# memory.net
KiCad netlist of a schematic drawn in Altium Designer
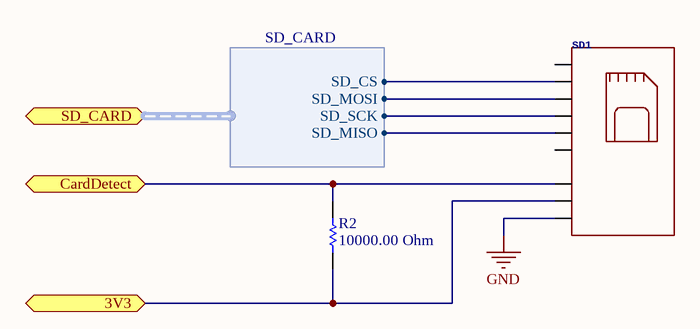
[diagram p0: memory.SchDoc]

(export (version "E")
  (design (tool "Eeschema 10.0.6"))
  (components
    (comp (ref "R2")
      (value "10000.00 Ohm")
      (footprint "RESC0402(1005)_N")
      (description "10K 0.063W 5% 0402 (1005 Metric)  SMD")
      (fields (field (name "POWER") "0.063 W") (field (name "TOLERANCE") "5 %"))
      (libsource (lib "Altium Content Vault") (part "CMP-1011-00081-1"))
    )
    (comp (ref "SD1")
      (value "Library:  MF_Connectors Description: SD Card Connector")
      (footprint "MF-MICROSD")
      (fields (field (name "HOUSEPART") "YES") (field (name "MPN") "MF-MICROSD"))
      (libsource (lib "MF_Connectors") (part "SD_CARD_SLOT_MICRO_RIGHT"))
    )
  )
  (nets
    (net (code "2") (name "/3V3") (class "Default")
      (node (ref "R2") (pin "1") (pinfunction "1_1") (pintype "passive"))
      (node (ref "SD1") (pin "PIN4") (pinfunction "3.3V_PIN4") (pintype "power_in"))
    )
    (net (code "3") (name "/CardDetect") (class "Default")
      (node (ref "R2") (pin "2") (pinfunction "2_2") (pintype "passive"))
      (node (ref "SD1") (pin "PIN9_PIN10") (pinfunction "CRD_DTCT_PIN9_PIN10") (pintype "passive"))
    )
    (net (code "4") (name "/SD_CS") (class "Default")
      (node (ref "SD1") (pin "PIN2") (pinfunction "CS_PIN2") (pintype "passive"))
    )
    (net (code "5") (name "/SD_MISO") (class "Default")
      (node (ref "SD1") (pin "PIN7") (pinfunction "D0_PIN7") (pintype "passive"))
    )
    (net (code "6") (name "/SD_MOSI") (class "Default")
      (node (ref "SD1") (pin "PIN3") (pinfunction "DI_PIN3") (pintype "passive"))
    )
    (net (code "7") (name "/SD_SCK") (class "Default")
      (node (ref "SD1") (pin "PIN5") (pinfunction "SCLK_PIN5") (pintype "passive"))
    )
    (net (code "9") (name "GND") (class "Default")
      (node (ref "SD1") (pin "G0_G1_PIN6") (pinfunction "GND_G0_G1_PIN6") (pintype "power_in"))
    )
    (net (code "10") (name "unconnected-(SD1-IRQ-PadPIN8)") (class "Default")
      (node (ref "SD1") (pin "PIN8") (pinfunction "IRQ_PIN8") (pintype "passive"))
    )
    (net (code "11") (name "unconnected-(SD1-RW-PadPIN1)") (class "Default")
      (node (ref "SD1") (pin "PIN1") (pinfunction "RW_PIN1") (pintype "passive"))
    )
  )
)
